# Main.net
KiCad netlist of a schematic drawn in Altium Designer
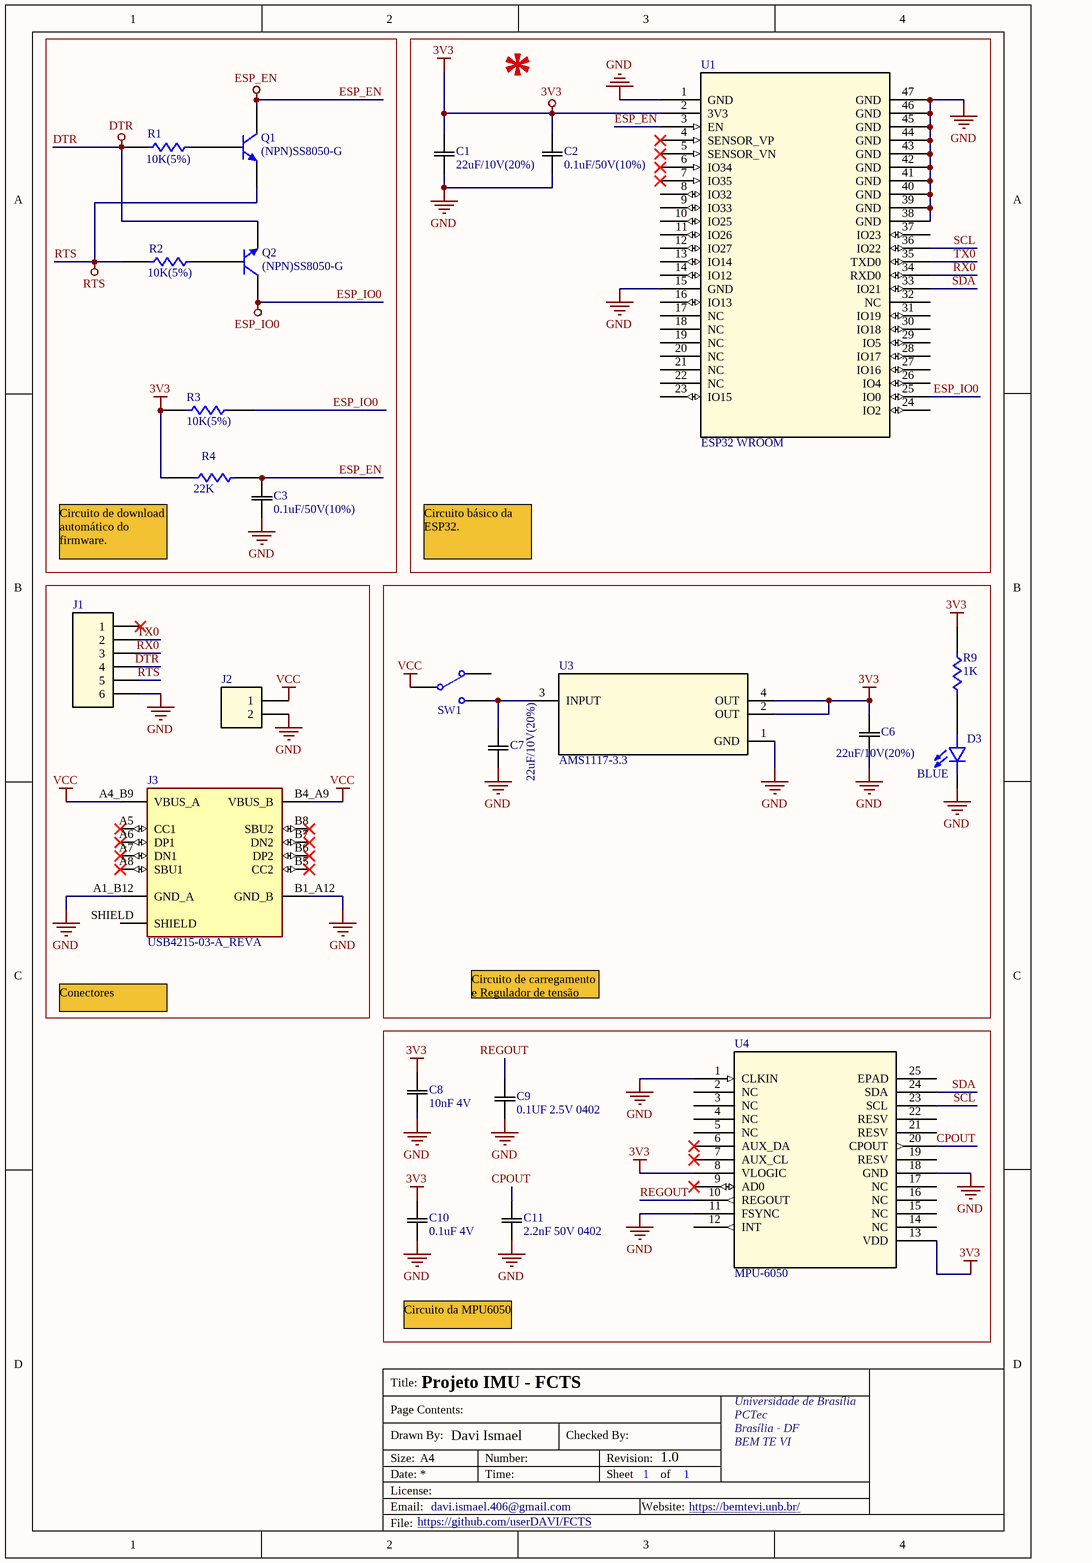
[diagram p0: Main.SchDoc]

(export (version "E")
  (design (tool "Eeschema 10.0.6"))
  (components
    (comp (ref "C1")
      (value "22uF/10V(20%)")
      (footprint "CAP_LMK212B_2X1P25_TAY-M")
      (description "No Description Available")
      (libsource (lib "Integrated_Library1") (part "LMK212BBJ226MG-T"))
    )
    (comp (ref "C2")
      (value "0.1uF/50V(10%)")
      (footprint "CC0603N_YAG")
      (description "No Description Available")
      (libsource (lib "Integrated_Library1") (part "CC0603KRX7R7BB104"))
    )
    (comp (ref "C3")
      (value "0.1uF/50V(10%)")
      (footprint "CC0603N_YAG")
      (description "No Description Available")
      (libsource (lib "Integrated_Library1") (part "CC0603KRX7R7BB104"))
    )
    (comp (ref "C6")
      (value "22uF/10V(20%)")
      (footprint "CAP_LMK212B_2X1P25_TAY-M")
      (description "No Description Available")
      (libsource (lib "Integrated_Library1") (part "LMK212BBJ226MG-T"))
    )
    (comp (ref "C7")
      (value "22uF/10V(20%)")
      (footprint "CAP_LMK212B_2X1P25_TAY-M")
      (description "No Description Available")
      (libsource (lib "Integrated_Library1") (part "LMK212BBJ226MG-T"))
    )
    (comp (ref "C8")
      (value "10nF 4V")
      (footprint "CAP_02013J0R1PBSTR500")
      (description "Ceramic, X7R, 10nF ±10%, 4V")
      (libsource (lib "Integrated_Library1") (part "02014D103KAT2A"))
    )
    (comp (ref "C9")
      (value "0.1UF 2.5V 0402")
      (footprint "CAPC0201X13N")
      (description "CAP CER 0.1UF 2.5V X7T 0402")
      (fields (field (name "MP") "GRM152D70E104KE19D"))
      (libsource (lib "Integrated_Library1") (part "GRM152D70E104KE19D"))
    )
    (comp (ref "C10")
      (value "0.1uF 4V")
      (footprint "CAPC1608X90N")
      (description "CAP CER 0.1UF 4V X7R 0603")
      (fields (field (name "MP") "06034C104KAT2A"))
      (libsource (lib "Integrated_Library1") (part "06034C104KAT2A"))
    )
    (comp (ref "C11")
      (value "2.2nF 50V 0402")
      (footprint "CAPC10555_55N_KEM")
      (description "CAP CER 0402 2.2NF 50V X7R 10%")
      (libsource (lib "Integrated_Library1") (part "C0402C222K5RECAUTO7411"))
    )
    (comp (ref "D3")
      (value "BLUE")
      (footprint "LED_KP-1608SURCK")
      (description "Single Color LEDs WL-SMCD SMD Mono SMD 0603 Blue 465nm")
      (fields (field (name "MF") "Kingbright") (field (name "MP") "KP-1608SURCK"))
      (libsource (lib "Integrated_Library1") (part "150060BS55040"))
    )
    (comp (ref "J1")
      (value "G800W302018EU")
      (footprint "CONN6x1_G800W302018EU_AMP")
      (description "No Description Available")
      (libsource (lib "Integrated_Library1") (part "G800W302018EU"))
    )
    (comp (ref "J2")
      (value "M20-9990246")
      (footprint "CONN2_M20-999_1x2_HRW")
      (description "header 2x1")
      (libsource (lib "Integrated_Library1") (part "M20-9990246"))
    )
    (comp (ref "J3")
      (value "USB4215-03-A_REVA")
      (footprint "GCT_USB4215-03-A_REVA")
      (description "Type C USB 2.0 Connector")
      (fields (field (name "MF") "Global Connector Technology") (field (name "MP") "USB4215-03-A"))
      (libsource (lib "Integrated_Library1") (part "USB4215-03-A_REVA"))
    )
    (comp (ref "Q1")
      (value "(NPN)SS8050-G")
      (footprint "(NPN)SS8050-G")
      (description "No Description Available")
      (libsource (lib "Integrated_Library1") (part "(NPN)SS8050-G"))
    )
    (comp (ref "Q2")
      (value "(NPN)SS8050-G")
      (footprint "(NPN)SS8050-G")
      (description "No Description Available")
      (libsource (lib "Integrated_Library1") (part "(NPN)SS8050-G"))
    )
    (comp (ref "R1")
      (value "10K(5%)")
      (footprint "STA_RMCF0603_STP-M")
      (description "No Description Available")
      (libsource (lib "Integrated_Library1") (part "RMCF0603JT10K0"))
    )
    (comp (ref "R2")
      (value "10K(5%)")
      (footprint "STA_RMCF0603_STP-M")
      (description "No Description Available")
      (libsource (lib "Integrated_Library1") (part "RMCF0603JT10K0"))
    )
    (comp (ref "R3")
      (value "10K(5%)")
      (footprint "STA_RMCF0603_STP-M")
      (description "No Description Available")
      (libsource (lib "Integrated_Library1") (part "RMCF0603JT10K0"))
    )
    (comp (ref "R4")
      (value "22K")
      (footprint "RC0603N_YAG")
      (description "No Description Available")
      (libsource (lib "Integrated_Library1") (part "RC0603FR-0722KL"))
    )
    (comp (ref "R9")
      (value "1K")
      (footprint "STA_RMCF0603_STP-M")
      (description "RES 1K")
      (libsource (lib "Integrated_Library1") (part "RK73H1JRTTD1001D"))
    )
    (comp (ref "SW1")
      (value "Mini Slide Switch")
      (footprint "450404015514")
      (description "WS-SLSU Mini Slide Switch, Same Side Connection Side Push, SPDT, 5VDC, 300mA, 240g")
      (fields
        (field (name "MANUFACTURER PART NUMBER") "450404015514")
        (field (name "MANUFACTURER") "Wurth Elektronik")
      )
      (libsource (lib "Integrated_Library1") (part "450404015514"))
    )
    (comp (ref "U1")
      (value "ESP32 WROOM")
      (footprint "MOD_ESP32-WROOM-32_EXP")
      (libsource (lib "Integrated_Library1") (part "ESP32 WROOM"))
    )
    (comp (ref "U3")
      (value "AMS1117-3.3")
      (footprint "AMS1117-3.3")
      (description "No Description Available")
      (libsource (lib "Integrated_Library1") (part "AMS1117-3.3"))
    )
    (comp (ref "U4")
      (value "MPU-6050")
      (footprint "QFN24_4X4X0P9-0P5_TDK-M")
      (description "No Description Available")
      (libsource (lib "Integrated_Library1") (part "MPU-6050"))
    )
  )
  (nets
    (net (code "1") (name "/CPOUT") (class "Default")
      (node (ref "C11") (pin "2") (pinfunction "2_2") (pintype "passive"))
      (node (ref "U4") (pin "20") (pinfunction "CPOUT_20") (pintype "output"))
    )
    (net (code "2") (name "/REGOUT") (class "Default")
      (node (ref "C9") (pin "2") (pinfunction "2_2") (pintype "passive"))
      (node (ref "U4") (pin "10") (pinfunction "REGOUT_10") (pintype "output"))
    )
    (net (code "3") (name "/RX0") (class "Default")
      (node (ref "J1") (pin "3") (pinfunction "3_3") (pintype "passive"))
      (node (ref "U1") (pin "34") (pinfunction "RXD0_34") (pintype "bidirectional"))
    )
    (net (code "4") (name "/SCL") (class "Default")
      (node (ref "U1") (pin "36") (pinfunction "IO22_36") (pintype "bidirectional"))
      (node (ref "U4") (pin "23") (pinfunction "SCL_23") (pintype "passive"))
    )
    (net (code "5") (name "/SDA") (class "Default")
      (node (ref "U1") (pin "33") (pinfunction "IO21_33") (pintype "bidirectional"))
      (node (ref "U4") (pin "24") (pinfunction "SDA_24") (pintype "passive"))
    )
    (net (code "6") (name "/TX0") (class "Default")
      (node (ref "J1") (pin "2") (pinfunction "2_2") (pintype "passive"))
      (node (ref "U1") (pin "35") (pinfunction "TXD0_35") (pintype "bidirectional"))
    )
    (net (code "7") (name "3V3") (class "Default")
      (node (ref "C1") (pin "2") (pinfunction "2_2") (pintype "passive"))
      (node (ref "C10") (pin "2") (pinfunction "2_2") (pintype "passive"))
      (node (ref "C2") (pin "2") (pinfunction "2_2") (pintype "passive"))
      (node (ref "C6") (pin "2") (pinfunction "2_2") (pintype "passive"))
      (node (ref "C8") (pin "2") (pinfunction "EPAD_2") (pintype "passive"))
      (node (ref "R3") (pin "2") (pinfunction "2_2") (pintype "passive"))
      (node (ref "R4") (pin "1") (pinfunction "1_1") (pintype "passive"))
      (node (ref "R9") (pin "1") (pinfunction "1_1") (pintype "passive"))
      (node (ref "U1") (pin "2") (pinfunction "3V3_2") (pintype "power_in"))
      (node (ref "U3") (pin "2") (pinfunction "OUT_2") (pintype "power_in"))
      (node (ref "U3") (pin "4") (pinfunction "OUT_4") (pintype "power_in"))
      (node (ref "U4") (pin "13") (pinfunction "VDD_13") (pintype "power_in"))
      (node (ref "U4") (pin "8") (pinfunction "VLOGIC_8") (pintype "power_in"))
    )
    (net (code "8") (name "DTR") (class "Default")
      (node (ref "J1") (pin "4") (pinfunction "4_4") (pintype "passive"))
      (node (ref "Q2") (pin "3") (pinfunction "E_3") (pintype "passive"))
      (node (ref "R1") (pin "1") (pinfunction "1_1") (pintype "passive"))
    )
    (net (code "9") (name "ESP_EN") (class "Default")
      (node (ref "C3") (pin "2") (pinfunction "2_2") (pintype "passive"))
      (node (ref "Q1") (pin "1") (pinfunction "C_1") (pintype "passive"))
      (node (ref "R4") (pin "2") (pinfunction "2_2") (pintype "passive"))
      (node (ref "U1") (pin "3") (pinfunction "EN_3") (pintype "input"))
    )
    (net (code "10") (name "ESP_IO0") (class "Default")
      (node (ref "Q2") (pin "1") (pinfunction "C_1") (pintype "passive"))
      (node (ref "R3") (pin "1") (pinfunction "1_1") (pintype "passive"))
      (node (ref "U1") (pin "25") (pinfunction "IO0_25") (pintype "bidirectional"))
    )
    (net (code "11") (name "GND") (class "Default")
      (node (ref "C1") (pin "1") (pinfunction "1_1") (pintype "passive"))
      (node (ref "C10") (pin "1") (pinfunction "1_1") (pintype "passive"))
      (node (ref "C11") (pin "1") (pinfunction "1_1") (pintype "passive"))
      (node (ref "C2") (pin "1") (pinfunction "1_1") (pintype "passive"))
      (node (ref "C3") (pin "1") (pinfunction "1_1") (pintype "passive"))
      (node (ref "C6") (pin "1") (pinfunction "1_1") (pintype "passive"))
      (node (ref "C7") (pin "1") (pinfunction "1_1") (pintype "passive"))
      (node (ref "C8") (pin "1") (pinfunction "EPAD_1") (pintype "passive"))
      (node (ref "C9") (pin "1") (pinfunction "1_1") (pintype "passive"))
      (node (ref "D3") (pin "2") (pinfunction "C_2") (pintype "passive"))
      (node (ref "J1") (pin "6") (pinfunction "6_6") (pintype "passive"))
      (node (ref "J2") (pin "2") (pinfunction "2_2") (pintype "passive"))
      (node (ref "J3") (pin "A1_B12") (pinfunction "GND_A_A1_B12") (pintype "power_in"))
      (node (ref "J3") (pin "B1_A12") (pinfunction "GND_B_B1_A12") (pintype "power_in"))
      (node (ref "U1") (pin "1") (pinfunction "GND_1") (pintype "power_in"))
      (node (ref "U1") (pin "15") (pinfunction "GND_15") (pintype "power_in"))
      (node (ref "U1") (pin "38") (pinfunction "GND_38") (pintype "power_in"))
      (node (ref "U1") (pin "39") (pinfunction "GND_39") (pintype "power_in"))
      (node (ref "U1") (pin "40") (pinfunction "GND_40") (pintype "power_in"))
      (node (ref "U1") (pin "41") (pinfunction "GND_41") (pintype "power_in"))
      (node (ref "U1") (pin "42") (pinfunction "GND_42") (pintype "power_in"))
      (node (ref "U1") (pin "43") (pinfunction "GND_43") (pintype "power_in"))
      (node (ref "U1") (pin "44") (pinfunction "GND_44") (pintype "power_in"))
      (node (ref "U1") (pin "45") (pinfunction "GND_45") (pintype "power_in"))
      (node (ref "U1") (pin "46") (pinfunction "GND_46") (pintype "power_in"))
      (node (ref "U1") (pin "47") (pinfunction "GND_47") (pintype "power_in"))
      (node (ref "U3") (pin "1") (pinfunction "GND_1") (pintype "power_in"))
      (node (ref "U4") (pin "1") (pinfunction "CLKIN_1") (pintype "input"))
      (node (ref "U4") (pin "11") (pinfunction "FSYNC_11") (pintype "passive"))
      (node (ref "U4") (pin "18") (pinfunction "GND_18") (pintype "power_in"))
    )
    (net (code "12") (name "Net-(D3-A)") (class "Default")
      (node (ref "D3") (pin "1") (pinfunction "A_1") (pintype "passive"))
      (node (ref "R9") (pin "2") (pinfunction "2_2") (pintype "passive"))
    )
    (net (code "13") (name "Net-(Q1-B)") (class "Default")
      (node (ref "Q1") (pin "2") (pinfunction "B_2") (pintype "passive"))
      (node (ref "R1") (pin "2") (pinfunction "2_2") (pintype "passive"))
    )
    (net (code "14") (name "Net-(Q2-B)") (class "Default")
      (node (ref "Q2") (pin "2") (pinfunction "B_2") (pintype "passive"))
      (node (ref "R2") (pin "2") (pinfunction "2_2") (pintype "passive"))
    )
    (net (code "15") (name "Net-(U3-INPUT)") (class "Default")
      (node (ref "C7") (pin "2") (pinfunction "2_2") (pintype "passive"))
      (node (ref "SW1") (pin "L2") (pinfunction "L2_L2") (pintype "passive"))
      (node (ref "U3") (pin "3") (pinfunction "INPUT_3") (pintype "power_in"))
    )
    (net (code "16") (name "RTS") (class "Default")
      (node (ref "J1") (pin "5") (pinfunction "5_5") (pintype "passive"))
      (node (ref "Q1") (pin "3") (pinfunction "E_3") (pintype "passive"))
      (node (ref "R2") (pin "1") (pinfunction "1_1") (pintype "passive"))
    )
    (net (code "17") (name "VCC") (class "Default")
      (node (ref "J2") (pin "1") (pinfunction "1_1") (pintype "passive"))
      (node (ref "J3") (pin "A4_B9") (pinfunction "VBUS_A_A4_B9") (pintype "power_in"))
      (node (ref "J3") (pin "B4_A9") (pinfunction "VBUS_B_B4_A9") (pintype "power_in"))
      (node (ref "SW1") (pin "COM") (pinfunction "COM_COM") (pintype "passive"))
    )
    (net (code "18") (name "unconnected-(J1-Pad1)") (class "Default")
      (node (ref "J1") (pin "1") (pinfunction "1_1") (pintype "passive+no_connect"))
    )
    (net (code "19") (name "unconnected-(J3-CC1-PadA5)") (class "Default")
      (node (ref "J3") (pin "A5") (pinfunction "CC1_A5") (pintype "bidirectional+no_connect"))
    )
    (net (code "20") (name "unconnected-(J3-CC2-PadB5)") (class "Default")
      (node (ref "J3") (pin "B5") (pinfunction "CC2_B5") (pintype "bidirectional+no_connect"))
    )
    (net (code "21") (name "unconnected-(J3-DN1-PadA7)") (class "Default")
      (node (ref "J3") (pin "A7") (pinfunction "DN1_A7") (pintype "bidirectional+no_connect"))
    )
    (net (code "22") (name "unconnected-(J3-DN2-PadB7)") (class "Default")
      (node (ref "J3") (pin "B7") (pinfunction "DN2_B7") (pintype "bidirectional+no_connect"))
    )
    (net (code "23") (name "unconnected-(J3-DP1-PadA6)") (class "Default")
      (node (ref "J3") (pin "A6") (pinfunction "DP1_A6") (pintype "bidirectional+no_connect"))
    )
    (net (code "24") (name "unconnected-(J3-DP2-PadB6)") (class "Default")
      (node (ref "J3") (pin "B6") (pinfunction "DP2_B6") (pintype "bidirectional+no_connect"))
    )
    (net (code "25") (name "unconnected-(J3-PadSHIELD)") (class "Default")
      (node (ref "J3") (pin "SHIELD") (pinfunction "SHIELD_SHIELD") (pintype "passive"))
    )
    (net (code "26") (name "unconnected-(J3-SBU1-PadA8)") (class "Default")
      (node (ref "J3") (pin "A8") (pinfunction "SBU1_A8") (pintype "bidirectional+no_connect"))
    )
    (net (code "27") (name "unconnected-(J3-SBU2-PadB8)") (class "Default")
      (node (ref "J3") (pin "B8") (pinfunction "SBU2_B8") (pintype "bidirectional+no_connect"))
    )
    (net (code "28") (name "unconnected-(SW1-PadL1)") (class "Default")
      (node (ref "SW1") (pin "L1") (pinfunction "L1_L1") (pintype "passive"))
    )
    (net (code "29") (name "unconnected-(U1-IO2-Pad24)") (class "Default")
      (node (ref "U1") (pin "24") (pinfunction "IO2_24") (pintype "bidirectional"))
    )
    (net (code "30") (name "unconnected-(U1-IO4-Pad26)") (class "Default")
      (node (ref "U1") (pin "26") (pinfunction "IO4_26") (pintype "bidirectional"))
    )
    (net (code "31") (name "unconnected-(U1-IO5-Pad29)") (class "Default")
      (node (ref "U1") (pin "29") (pinfunction "IO5_29") (pintype "bidirectional"))
    )
    (net (code "32") (name "unconnected-(U1-IO12-Pad14)") (class "Default")
      (node (ref "U1") (pin "14") (pinfunction "IO12_14") (pintype "bidirectional"))
    )
    (net (code "33") (name "unconnected-(U1-IO13-Pad16)") (class "Default")
      (node (ref "U1") (pin "16") (pinfunction "IO13_16") (pintype "bidirectional"))
    )
    (net (code "34") (name "unconnected-(U1-IO14-Pad13)") (class "Default")
      (node (ref "U1") (pin "13") (pinfunction "IO14_13") (pintype "bidirectional"))
    )
    (net (code "35") (name "unconnected-(U1-IO15-Pad23)") (class "Default")
      (node (ref "U1") (pin "23") (pinfunction "IO15_23") (pintype "bidirectional"))
    )
    (net (code "36") (name "unconnected-(U1-IO16-Pad27)") (class "Default")
      (node (ref "U1") (pin "27") (pinfunction "IO16_27") (pintype "bidirectional"))
    )
    (net (code "37") (name "unconnected-(U1-IO17-Pad28)") (class "Default")
      (node (ref "U1") (pin "28") (pinfunction "IO17_28") (pintype "bidirectional"))
    )
    (net (code "38") (name "unconnected-(U1-IO18-Pad30)") (class "Default")
      (node (ref "U1") (pin "30") (pinfunction "IO18_30") (pintype "bidirectional"))
    )
    (net (code "39") (name "unconnected-(U1-IO19-Pad31)") (class "Default")
      (node (ref "U1") (pin "31") (pinfunction "IO19_31") (pintype "bidirectional"))
    )
    (net (code "40") (name "unconnected-(U1-IO23-Pad37)") (class "Default")
      (node (ref "U1") (pin "37") (pinfunction "IO23_37") (pintype "bidirectional"))
    )
    (net (code "41") (name "unconnected-(U1-IO25-Pad10)") (class "Default")
      (node (ref "U1") (pin "10") (pinfunction "IO25_10") (pintype "bidirectional"))
    )
    (net (code "42") (name "unconnected-(U1-IO26-Pad11)") (class "Default")
      (node (ref "U1") (pin "11") (pinfunction "IO26_11") (pintype "bidirectional"))
    )
    (net (code "43") (name "unconnected-(U1-IO27-Pad12)") (class "Default")
      (node (ref "U1") (pin "12") (pinfunction "IO27_12") (pintype "bidirectional"))
    )
    (net (code "44") (name "unconnected-(U1-IO32-Pad8)") (class "Default")
      (node (ref "U1") (pin "8") (pinfunction "IO32_8") (pintype "bidirectional"))
    )
    (net (code "45") (name "unconnected-(U1-IO33-Pad9)") (class "Default")
      (node (ref "U1") (pin "9") (pinfunction "IO33_9") (pintype "bidirectional"))
    )
    (net (code "46") (name "unconnected-(U1-IO34-Pad6)") (class "Default")
      (node (ref "U1") (pin "6") (pinfunction "IO34_6") (pintype "input+no_connect"))
    )
    (net (code "47") (name "unconnected-(U1-IO35-Pad7)") (class "Default")
      (node (ref "U1") (pin "7") (pinfunction "IO35_7") (pintype "input+no_connect"))
    )
    (net (code "48") (name "unconnected-(U1-NC-Pad17)") (class "Default")
      (node (ref "U1") (pin "17") (pinfunction "NC_17") (pintype "passive"))
    )
    (net (code "49") (name "unconnected-(U1-NC-Pad18)") (class "Default")
      (node (ref "U1") (pin "18") (pinfunction "NC_18") (pintype "passive"))
    )
    (net (code "50") (name "unconnected-(U1-NC-Pad19)") (class "Default")
      (node (ref "U1") (pin "19") (pinfunction "NC_19") (pintype "passive"))
    )
    (net (code "51") (name "unconnected-(U1-NC-Pad20)") (class "Default")
      (node (ref "U1") (pin "20") (pinfunction "NC_20") (pintype "passive"))
    )
    (net (code "52") (name "unconnected-(U1-NC-Pad21)") (class "Default")
      (node (ref "U1") (pin "21") (pinfunction "NC_21") (pintype "passive"))
    )
    (net (code "53") (name "unconnected-(U1-NC-Pad22)") (class "Default")
      (node (ref "U1") (pin "22") (pinfunction "NC_22") (pintype "passive"))
    )
    (net (code "54") (name "unconnected-(U1-NC-Pad32)") (class "Default")
      (node (ref "U1") (pin "32") (pinfunction "NC_32") (pintype "passive"))
    )
    (net (code "55") (name "unconnected-(U1-SENSOR_VN-Pad5)") (class "Default")
      (node (ref "U1") (pin "5") (pinfunction "SENSOR_VN_5") (pintype "input+no_connect"))
    )
    (net (code "56") (name "unconnected-(U1-SENSOR_VP-Pad4)") (class "Default")
      (node (ref "U1") (pin "4") (pinfunction "SENSOR_VP_4") (pintype "input+no_connect"))
    )
    (net (code "57") (name "unconnected-(U4-AD0-Pad9)") (class "Default")
      (node (ref "U4") (pin "9") (pinfunction "AD0_9") (pintype "bidirectional+no_connect"))
    )
    (net (code "58") (name "unconnected-(U4-AUX_CL-Pad7)") (class "Default")
      (node (ref "U4") (pin "7") (pinfunction "AUX_CL_7") (pintype "passive+no_connect"))
    )
    (net (code "59") (name "unconnected-(U4-AUX_DA-Pad6)") (class "Default")
      (node (ref "U4") (pin "6") (pinfunction "AUX_DA_6") (pintype "passive+no_connect"))
    )
    (net (code "60") (name "unconnected-(U4-EPAD-Pad25)") (class "Default")
      (node (ref "U4") (pin "25") (pinfunction "EPAD_25") (pintype "passive"))
    )
    (net (code "61") (name "unconnected-(U4-INT-Pad12)") (class "Default")
      (node (ref "U4") (pin "12") (pinfunction "INT_12") (pintype "output"))
    )
    (net (code "62") (name "unconnected-(U4-NC-Pad2)") (class "Default")
      (node (ref "U4") (pin "2") (pinfunction "NC_2") (pintype "passive"))
    )
    (net (code "63") (name "unconnected-(U4-NC-Pad3)") (class "Default")
      (node (ref "U4") (pin "3") (pinfunction "NC_3") (pintype "passive"))
    )
    (net (code "64") (name "unconnected-(U4-NC-Pad4)") (class "Default")
      (node (ref "U4") (pin "4") (pinfunction "NC_4") (pintype "passive"))
    )
    (net (code "65") (name "unconnected-(U4-NC-Pad5)") (class "Default")
      (node (ref "U4") (pin "5") (pinfunction "NC_5") (pintype "passive"))
    )
    (net (code "66") (name "unconnected-(U4-NC-Pad14)") (class "Default")
      (node (ref "U4") (pin "14") (pinfunction "NC_14") (pintype "passive"))
    )
    (net (code "67") (name "unconnected-(U4-NC-Pad15)") (class "Default")
      (node (ref "U4") (pin "15") (pinfunction "NC_15") (pintype "passive"))
    )
    (net (code "68") (name "unconnected-(U4-NC-Pad16)") (class "Default")
      (node (ref "U4") (pin "16") (pinfunction "NC_16") (pintype "passive"))
    )
    (net (code "69") (name "unconnected-(U4-NC-Pad17)") (class "Default")
      (node (ref "U4") (pin "17") (pinfunction "NC_17") (pintype "passive"))
    )
    (net (code "70") (name "unconnected-(U4-RESV-Pad19)") (class "Default")
      (node (ref "U4") (pin "19") (pinfunction "RESV_19") (pintype "passive"))
    )
    (net (code "71") (name "unconnected-(U4-RESV-Pad21)") (class "Default")
      (node (ref "U4") (pin "21") (pinfunction "RESV_21") (pintype "passive"))
    )
    (net (code "72") (name "unconnected-(U4-RESV-Pad22)") (class "Default")
      (node (ref "U4") (pin "22") (pinfunction "RESV_22") (pintype "passive"))
    )
  )
)
